# Main_IC_Sheet.net
KiCad netlist of a schematic drawn in Altium Designer
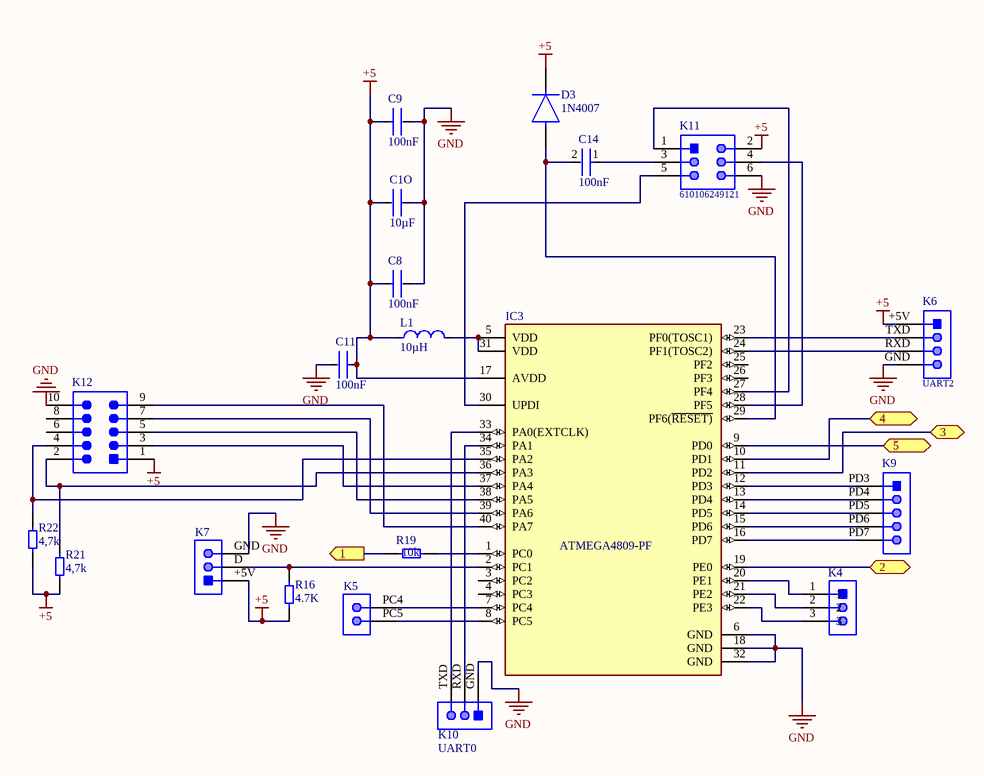
[diagram p0: Main_IC_Sheet.SchDoc]

(export (version "E")
  (design (tool "Eeschema 10.0.6"))
  (components
    (comp (ref "C1O")
      (value "10µF")
      (footprint "CAPPRD200W52D525H1200")
      (description "CAP CER 0.1UF 50V X7R 0805")
      (fields
        (field (name "MANUFACTURER PART NUMBER") "C0805C104K5RACTU")
        (field (name "MANUFACTURER") "KEMET")
      )
      (libsource (lib "Soldeerstation") (part "CMP-2007-00279-2"))
    )
    (comp (ref "C8")
      (value "100nF")
      (footprint "FP-C0805C-DN-IPC_A")
      (description "CAP CER 0.1UF 50V X7R 0805")
      (fields
        (field (name "MANUFACTURER PART NUMBER") "C0805C104K5RACTU")
        (field (name "MANUFACTURER") "KEMET")
      )
      (libsource (lib "Soldeerstation") (part "CMP-2007-00279-2"))
    )
    (comp (ref "C9")
      (value "100nF")
      (footprint "FP-C0805C-DN-IPC_A")
      (description "CAP CER 0.1UF 50V X7R 0805")
      (fields
        (field (name "MANUFACTURER PART NUMBER") "C0805C104K5RACTU")
        (field (name "MANUFACTURER") "KEMET")
      )
      (libsource (lib "Soldeerstation") (part "CMP-2007-00279-2"))
    )
    (comp (ref "C11")
      (value "100nF")
      (footprint "FP-C0805C-DN-IPC_A")
      (description "CAP CER 0.1UF 50V X7R 0805")
      (fields
        (field (name "MANUFACTURER PART NUMBER") "C0805C104K5RACTU")
        (field (name "MANUFACTURER") "KEMET")
      )
      (libsource (lib "Soldeerstation") (part "CMP-2007-00279-2"))
    )
    (comp (ref "C14")
      (value "100nF")
      (footprint "FP-C0805C-DN-IPC_A")
      (description "CAP CER 0.1UF 50V X7R 0805")
      (fields
        (field (name "MANUFACTURER PART NUMBER") "C0805C104K5RACTU")
        (field (name "MANUFACTURER") "KEMET")
      )
      (libsource (lib "") (part "CMP-2007-00279-2_1"))
    )
    (comp (ref "D3")
      (value "1N4007")
      (footprint "FP-1N4007-MFG")
      (description "Rectifier diode 1000 V 1 A DO-41, ,")
      (fields
        (field (name "MANUFACTURER") "Diotec")
        (field (name "OCTOPART") "https://octopart.com/1n4007-diotec-4040411")
      )
      (libsource (lib "Soldeerstation") (part "CMP-123542-000001-1"))
    )
    (comp (ref "IC3")
      (value "ATMEGA4809-PF")
      (footprint "FP-C04-016-MFG")
      (description "IC MCU 8BIT 48KB FLASH 40DIP")
      (libsource (lib "Soldeerstation") (part "CMP-06276-000616-1"))
    )
    (comp (ref "K4")
      (value "~")
      (footprint "MOLX-22-28-4033_V")
      (description "Male Header, Pitch 2.54 mm, 1 x 3 Position, Height 8.38 mm, Tail Length 3.18 mm, RoHS, Bulk")
      (fields (field (name "MANUFACTURER") "Molex"))
      (libsource (lib "") (part "CMP-1676-00001-5_2"))
    )
    (comp (ref "K5")
      (value "~")
      (footprint "TECO-5-146280-2_V")
      (fields (field (name "MANUFACTURER") "TE Connectivity"))
      (libsource (lib "Soldeerstation") (part "CMP-2000-07492-1"))
    )
    (comp (ref "K6")
      (value "UART2")
      (footprint "61300411121")
      (description "THT Vertical Pin Header WR-PHD, Pitch 2.54 mm, Single Row, 4 pins")
      (fields
        (field (name "MANUFACTURER") "Wurth Elektronik")
        (field (name "PART NUMBER") "61300411121")
        (field (name "PUBLISHER") "WurthElektronik")
      )
      (libsource (lib "Soldeerstation") (part "CMP-1502-01064-1"))
    )
    (comp (ref "K7")
      (value "~")
      (footprint "MOLX-22-28-4033_V")
      (description "Male Header, Pitch 2.54 mm, 1 x 3 Position, Height 8.38 mm, Tail Length 3.18 mm, RoHS, Bulk")
      (fields (field (name "MANUFACTURER") "Molex"))
      (libsource (lib "Soldeerstation") (part "CMP-1676-00001-5"))
    )
    (comp (ref "K9")
      (value "691701320005B")
      (footprint "61300511121")
      (description "Serie 7013 B - 3.81mm Vertical PCB Header THR Type with Flanges WR-TBL, 5 pin")
      (fields (field (name "MANUFACTURER") "Wurth Elektronik") (field (name "PUBLISHER") "WurthElektronik"))
      (libsource (lib "Soldeerstation") (part "CMP-1502-01995-1"))
    )
    (comp (ref "K10")
      (value "UART0")
      (footprint "MOLX-22-28-4033_V")
      (description "Male Header, Pitch 2.54 mm, 1 x 3 Position, Height 8.38 mm, Tail Length 3.18 mm, RoHS, Bulk")
      (fields (field (name "MANUFACTURER") "Molex"))
      (libsource (lib "") (part "CMP-1676-00001-5_1"))
    )
    (comp (ref "K11")
      (value "610106249121")
      (footprint "SMTC-TSW-103-08-L-D_V")
      (description "SMT Angled Pin Header WR-PHD, Pitch 2.54 mm, Dual Row, 6 pins")
      (fields (field (name "MANUFACTURER") "Wurth Elektronik") (field (name "PUBLISHER") "WurthElektronik"))
      (libsource (lib "Soldeerstation") (part "CMP-1502-01146-1"))
    )
    (comp (ref "K12")
      (value "~")
      (footprint "TECO-1-1634688-0-10_V")
      (fields (field (name "MANUFACTURER") "TE Connectivity") (field (name "PARTNUMBER") "1-1634688-0"))
      (libsource (lib "Soldeerstation") (part "CMP-2000-05854-1"))
    )
    (comp (ref "L1")
      (value "10µH")
      (footprint "FP-IR02-MFG")
      (description "IR-2 10 10% B08")
      (fields (field (name "TOLERANCE") "10%") (field (name "OBSOLETE PART") "true"))
      (libsource (lib "Soldeerstation") (part "CMP-03630-000001-1"))
    )
    (comp (ref "R16")
      (value "4.7K")
      (footprint "RESC2013X60X40ML20T25")
      (fields (field (name "PART NUMBER") "ERA6AEB332V") (field (name "MANUFACTURER") "Panasonic"))
      (libsource (lib "Soldeerstation") (part "CMP-2001-00629-1_1"))
    )
    (comp (ref "R19")
      (value "10k")
      (footprint "RESC2013X60X40ML20T25")
      (fields (field (name "PART NUMBER") "ERA6AEB332V") (field (name "MANUFACTURER") "Panasonic"))
      (libsource (lib "Soldeerstation") (part "CMP-2001-00629-1_1"))
    )
    (comp (ref "R21")
      (value "4,7k")
      (footprint "RESC2013X60X40ML20T25")
      (fields (field (name "PART NUMBER") "ERA6AEB332V") (field (name "MANUFACTURER") "Panasonic"))
      (libsource (lib "Soldeerstation") (part "CMP-2001-00629-1_1"))
    )
    (comp (ref "R22")
      (value "4,7k")
      (footprint "RESC2013X60X40ML20T25")
      (fields (field (name "PART NUMBER") "ERA6AEB332V") (field (name "MANUFACTURER") "Panasonic"))
      (libsource (lib "Soldeerstation") (part "CMP-2001-00629-1_1"))
    )
  )
  (nets
    (net (code "1") (name "+5") (class "Default")
      (node (ref "C11") (pin "1") (pinfunction "1_1") (pintype "passive"))
      (node (ref "C1O") (pin "2") (pinfunction "2_2") (pintype "passive"))
      (node (ref "C8") (pin "1") (pinfunction "1_1") (pintype "passive"))
      (node (ref "C9") (pin "1") (pinfunction "1_1") (pintype "passive"))
      (node (ref "D3") (pin "1") (pinfunction "C_1") (pintype "passive"))
      (node (ref "IC3") (pin "17") (pinfunction "AVDD_17") (pintype "power_in"))
      (node (ref "K11") (pin "2") (pinfunction "2_2") (pintype "passive"))
      (node (ref "K12") (pin "1") (pinfunction "1_1") (pintype "passive"))
      (node (ref "K6") (pin "+5V") (pinfunction "1_+5V") (pintype "passive"))
      (node (ref "K7") (pin "+5V") (pinfunction "3_+5V") (pintype "passive"))
      (node (ref "L1") (pin "1") (pinfunction "1_1") (pintype "passive"))
      (node (ref "R16") (pin "2") (pinfunction "2_2") (pintype "passive"))
      (node (ref "R21") (pin "1") (pinfunction "1_1") (pintype "passive"))
      (node (ref "R22") (pin "1") (pinfunction "1_1") (pintype "passive"))
    )
    (net (code "2") (name "/1") (class "Default")
      (node (ref "R19") (pin "1") (pinfunction "1_1") (pintype "passive"))
    )
    (net (code "3") (name "/2") (class "Default")
      (node (ref "IC3") (pin "19") (pinfunction "PE0_19") (pintype "bidirectional"))
    )
    (net (code "4") (name "/3") (class "Default")
      (node (ref "IC3") (pin "11") (pinfunction "PD2_11") (pintype "bidirectional"))
    )
    (net (code "5") (name "/4") (class "Default")
      (node (ref "IC3") (pin "10") (pinfunction "PD1_10") (pintype "bidirectional"))
    )
    (net (code "6") (name "/5") (class "Default")
      (node (ref "IC3") (pin "9") (pinfunction "PD0_9") (pintype "bidirectional"))
    )
    (net (code "7") (name "GND") (class "Default")
      (node (ref "C11") (pin "2") (pinfunction "2_2") (pintype "passive"))
      (node (ref "C1O") (pin "1") (pinfunction "1_1") (pintype "passive"))
      (node (ref "C8") (pin "2") (pinfunction "2_2") (pintype "passive"))
      (node (ref "C9") (pin "2") (pinfunction "2_2") (pintype "passive"))
      (node (ref "IC3") (pin "18") (pinfunction "GND_18") (pintype "power_in"))
      (node (ref "IC3") (pin "32") (pinfunction "GND_32") (pintype "power_in"))
      (node (ref "IC3") (pin "6") (pinfunction "GND_6") (pintype "power_in"))
      (node (ref "K10") (pin "GND") (pinfunction "1_GND") (pintype "passive"))
      (node (ref "K11") (pin "6") (pinfunction "6_6") (pintype "passive"))
      (node (ref "K12") (pin "10") (pinfunction "10_10") (pintype "passive"))
      (node (ref "K6") (pin "GND") (pinfunction "4_GND") (pintype "passive"))
      (node (ref "K7") (pin "GND") (pinfunction "1_GND") (pintype "passive"))
    )
    (net (code "8") (name "Net-(C14-Pad1)") (class "Default")
      (node (ref "C14") (pin "1") (pinfunction "1_1") (pintype "passive"))
      (node (ref "K11") (pin "3") (pinfunction "3_3") (pintype "passive"))
    )
    (net (code "9") (name "Net-(D3-A)") (class "Default")
      (node (ref "C14") (pin "2") (pinfunction "2_2") (pintype "passive"))
      (node (ref "D3") (pin "2") (pinfunction "A_2") (pintype "passive"))
      (node (ref "IC3") (pin "29") (pinfunction "PF6(~{RESET)}_29") (pintype "bidirectional"))
    )
    (net (code "10") (name "Net-(IC3-PA0(EXTCLK))") (class "Default")
      (node (ref "IC3") (pin "33") (pinfunction "PA0(EXTCLK)_33") (pintype "bidirectional"))
      (node (ref "K10") (pin "TXD") (pinfunction "3_TXD") (pintype "passive"))
    )
    (net (code "11") (name "Net-(IC3-PA1)") (class "Default")
      (node (ref "IC3") (pin "34") (pinfunction "PA1_34") (pintype "bidirectional"))
      (node (ref "K10") (pin "RXD") (pinfunction "2_RXD") (pintype "passive"))
    )
    (net (code "12") (name "Net-(IC3-PA2)") (class "Default")
      (node (ref "IC3") (pin "35") (pinfunction "PA2_35") (pintype "bidirectional"))
      (node (ref "K12") (pin "4") (pinfunction "4_4") (pintype "passive"))
      (node (ref "R22") (pin "2") (pinfunction "2_2") (pintype "passive"))
    )
    (net (code "13") (name "Net-(IC3-PA3)") (class "Default")
      (node (ref "IC3") (pin "36") (pinfunction "PA3_36") (pintype "bidirectional"))
      (node (ref "K12") (pin "2") (pinfunction "2_2") (pintype "passive"))
      (node (ref "R21") (pin "2") (pinfunction "2_2") (pintype "passive"))
    )
    (net (code "14") (name "Net-(IC3-PA4)") (class "Default")
      (node (ref "IC3") (pin "37") (pinfunction "PA4_37") (pintype "bidirectional"))
      (node (ref "K12") (pin "3") (pinfunction "3_3") (pintype "passive"))
    )
    (net (code "15") (name "Net-(IC3-PA5)") (class "Default")
      (node (ref "IC3") (pin "38") (pinfunction "PA5_38") (pintype "bidirectional"))
      (node (ref "K12") (pin "5") (pinfunction "5_5") (pintype "passive"))
    )
    (net (code "16") (name "Net-(IC3-PA6)") (class "Default")
      (node (ref "IC3") (pin "39") (pinfunction "PA6_39") (pintype "bidirectional"))
      (node (ref "K12") (pin "7") (pinfunction "7_7") (pintype "passive"))
    )
    (net (code "17") (name "Net-(IC3-PA7)") (class "Default")
      (node (ref "IC3") (pin "40") (pinfunction "PA7_40") (pintype "bidirectional"))
      (node (ref "K12") (pin "9") (pinfunction "9_9") (pintype "passive"))
    )
    (net (code "18") (name "Net-(IC3-PC0)") (class "Default")
      (node (ref "IC3") (pin "1") (pinfunction "PC0_1") (pintype "bidirectional"))
      (node (ref "R19") (pin "2") (pinfunction "2_2") (pintype "passive"))
    )
    (net (code "19") (name "Net-(IC3-PC1)") (class "Default")
      (node (ref "IC3") (pin "2") (pinfunction "PC1_2") (pintype "bidirectional"))
      (node (ref "K7") (pin "D") (pinfunction "2_D") (pintype "passive"))
      (node (ref "R16") (pin "1") (pinfunction "1_1") (pintype "passive"))
    )
    (net (code "20") (name "Net-(IC3-PC4)") (class "Default")
      (node (ref "IC3") (pin "7") (pinfunction "PC4_7") (pintype "bidirectional"))
      (node (ref "K5") (pin "PC4") (pinfunction "2_PC4") (pintype "passive"))
    )
    (net (code "21") (name "Net-(IC3-PC5)") (class "Default")
      (node (ref "IC3") (pin "8") (pinfunction "PC5_8") (pintype "bidirectional"))
      (node (ref "K5") (pin "PC5") (pinfunction "1_PC5") (pintype "passive"))
    )
    (net (code "22") (name "Net-(IC3-PD3)") (class "Default")
      (node (ref "IC3") (pin "12") (pinfunction "PD3_12") (pintype "bidirectional"))
      (node (ref "K9") (pin "PD3") (pinfunction "1_PD3") (pintype "passive"))
    )
    (net (code "23") (name "Net-(IC3-PD4)") (class "Default")
      (node (ref "IC3") (pin "13") (pinfunction "PD4_13") (pintype "bidirectional"))
      (node (ref "K9") (pin "PD4") (pinfunction "2_PD4") (pintype "passive"))
    )
    (net (code "24") (name "Net-(IC3-PD5)") (class "Default")
      (node (ref "IC3") (pin "14") (pinfunction "PD5_14") (pintype "bidirectional"))
      (node (ref "K9") (pin "PD5") (pinfunction "3_PD5") (pintype "passive"))
    )
    (net (code "25") (name "Net-(IC3-PD6)") (class "Default")
      (node (ref "IC3") (pin "15") (pinfunction "PD6_15") (pintype "bidirectional"))
      (node (ref "K9") (pin "PD6") (pinfunction "4_PD6") (pintype "passive"))
    )
    (net (code "26") (name "Net-(IC3-PD7)") (class "Default")
      (node (ref "IC3") (pin "16") (pinfunction "PD7_16") (pintype "bidirectional"))
      (node (ref "K9") (pin "PD7") (pinfunction "5_PD7") (pintype "passive"))
    )
    (net (code "27") (name "Net-(IC3-PE1)") (class "Default")
      (node (ref "IC3") (pin "20") (pinfunction "PE1_20") (pintype "bidirectional"))
      (node (ref "K4") (pin "1") (pinfunction "1_1") (pintype "passive"))
    )
    (net (code "28") (name "Net-(IC3-PE2)") (class "Default")
      (node (ref "IC3") (pin "21") (pinfunction "PE2_21") (pintype "bidirectional"))
      (node (ref "K4") (pin "2") (pinfunction "2_2") (pintype "passive"))
    )
    (net (code "29") (name "Net-(IC3-PE3)") (class "Default")
      (node (ref "IC3") (pin "22") (pinfunction "PE3_22") (pintype "bidirectional"))
      (node (ref "K4") (pin "3") (pinfunction "3_3") (pintype "passive"))
    )
    (net (code "30") (name "Net-(IC3-PF0(TOSC1))") (class "Default")
      (node (ref "IC3") (pin "23") (pinfunction "PF0(TOSC1)_23") (pintype "bidirectional"))
      (node (ref "K6") (pin "TXD") (pinfunction "2_TXD") (pintype "passive"))
    )
    (net (code "31") (name "Net-(IC3-PF1(TOSC2))") (class "Default")
      (node (ref "IC3") (pin "24") (pinfunction "PF1(TOSC2)_24") (pintype "bidirectional"))
      (node (ref "K6") (pin "RXD") (pinfunction "3_RXD") (pintype "passive"))
    )
    (net (code "32") (name "Net-(IC3-PF4)") (class "Default")
      (node (ref "IC3") (pin "27") (pinfunction "PF4_27") (pintype "bidirectional"))
      (node (ref "K11") (pin "1") (pinfunction "1_1") (pintype "passive"))
    )
    (net (code "33") (name "Net-(IC3-PF5)") (class "Default")
      (node (ref "IC3") (pin "28") (pinfunction "PF5_28") (pintype "bidirectional"))
      (node (ref "K11") (pin "4") (pinfunction "4_4") (pintype "passive"))
    )
    (net (code "34") (name "Net-(IC3-UPDI)") (class "Default")
      (node (ref "IC3") (pin "30") (pinfunction "UPDI_30") (pintype "passive"))
      (node (ref "K11") (pin "5") (pinfunction "5_5") (pintype "passive"))
    )
    (net (code "35") (name "Net-(IC3-VDD-Pad31)") (class "Default")
      (node (ref "IC3") (pin "31") (pinfunction "VDD_31") (pintype "power_in"))
      (node (ref "IC3") (pin "5") (pinfunction "VDD_5") (pintype "power_in"))
      (node (ref "L1") (pin "2") (pinfunction "2_2") (pintype "passive"))
    )
    (net (code "36") (name "unconnected-(IC3-PC2-Pad3)") (class "Default")
      (node (ref "IC3") (pin "3") (pinfunction "PC2_3") (pintype "bidirectional"))
    )
    (net (code "37") (name "unconnected-(IC3-PC3-Pad4)") (class "Default")
      (node (ref "IC3") (pin "4") (pinfunction "PC3_4") (pintype "bidirectional"))
    )
    (net (code "38") (name "unconnected-(IC3-PF2-Pad25)") (class "Default")
      (node (ref "IC3") (pin "25") (pinfunction "PF2_25") (pintype "bidirectional"))
    )
    (net (code "39") (name "unconnected-(IC3-PF3-Pad26)") (class "Default")
      (node (ref "IC3") (pin "26") (pinfunction "PF3_26") (pintype "bidirectional"))
    )
    (net (code "40") (name "unconnected-(K12-Pad6)") (class "Default")
      (node (ref "K12") (pin "6") (pinfunction "6_6") (pintype "passive"))
    )
    (net (code "41") (name "unconnected-(K12-Pad8)") (class "Default")
      (node (ref "K12") (pin "8") (pinfunction "8_8") (pintype "passive"))
    )
  )
)
